# ST-Link_v3_devkit.net
KiCad netlist of a schematic drawn in EasyEDA Pro
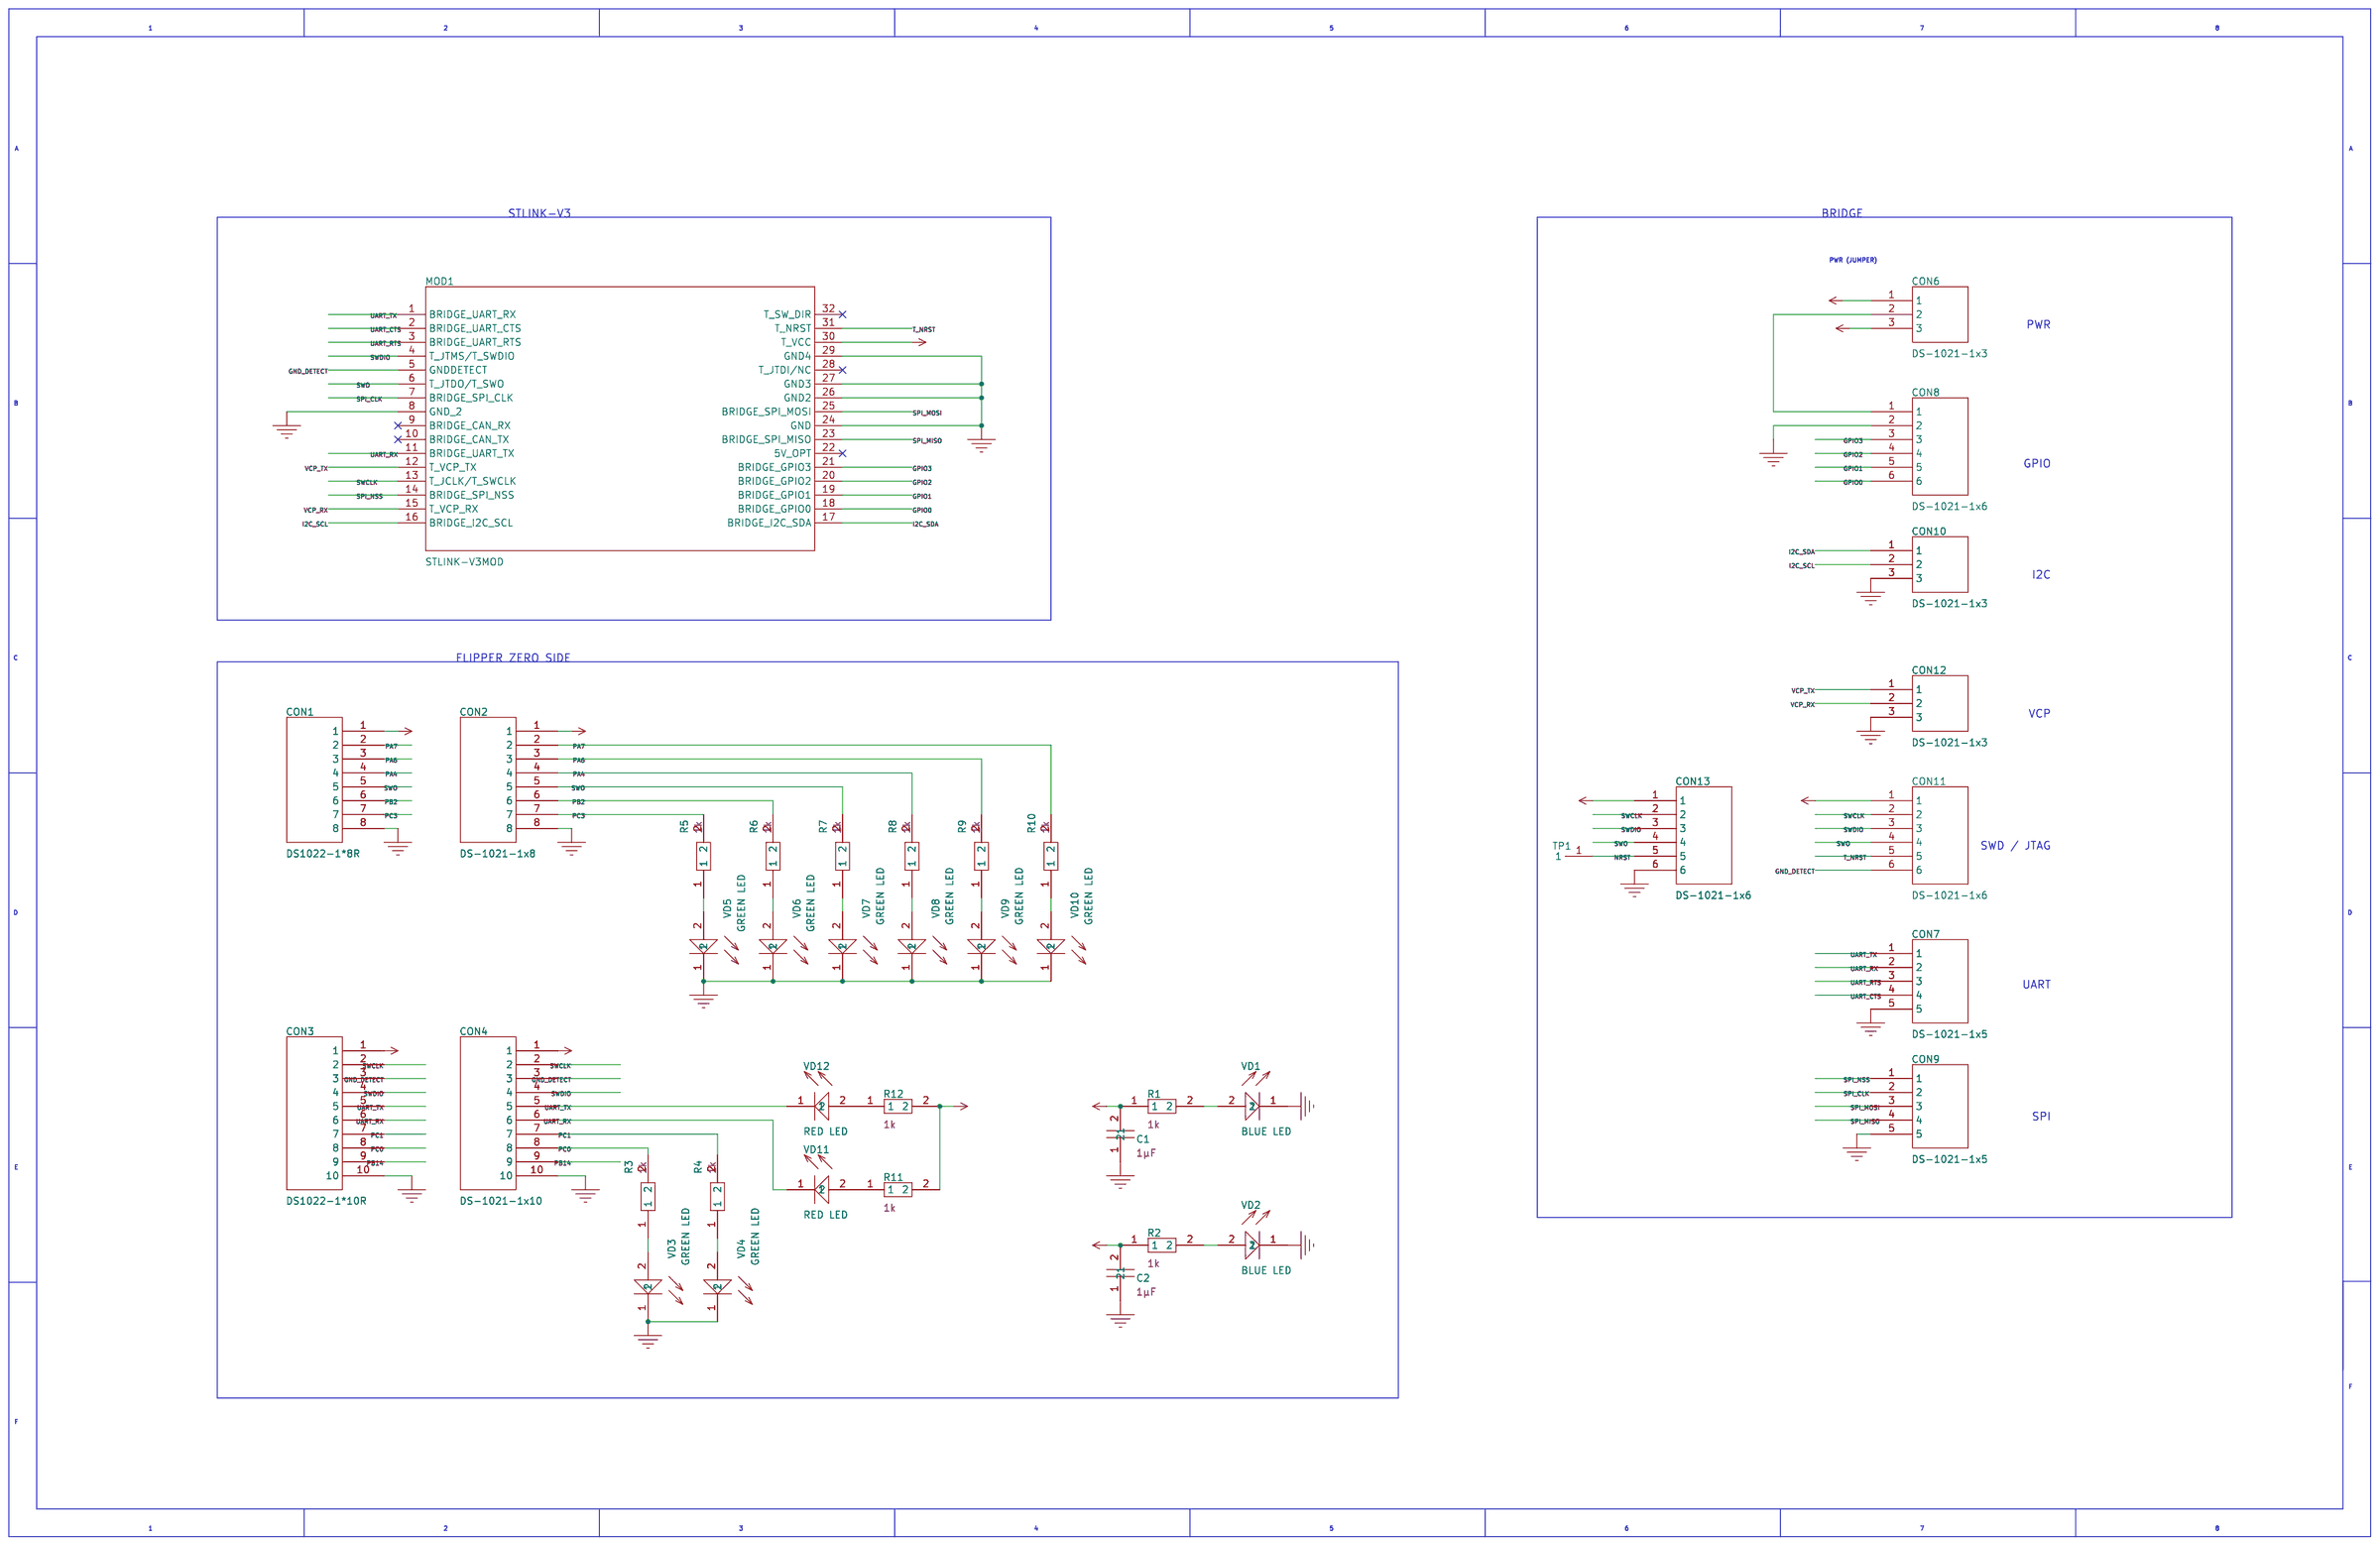
[diagram p0: schematic sheet]

(export (version "E")
  (design (tool "Eeschema 10.0.6"))
  (components
    (comp (ref "C1")
      (value "1µF")
      (footprint "easyedapro:Capacitor_SMD:C_0603_1608Metric")
      (description "Chip Capacitor")
      (fields (field (name "TOLERANCE") "10%") (field (name "VOLTAGE") "16V"))
      (libsource (lib "easyedapro") (part "ST-Link_3.0_devkit-altium-import_root_1_Symbol"))
    )
    (comp (ref "C2")
      (value "1µF")
      (footprint "easyedapro:Capacitor_SMD:C_0603_1608Metric")
      (description "Chip Capacitor")
      (fields (field (name "TOLERANCE") "10%") (field (name "VOLTAGE") "16V"))
      (libsource (lib "easyedapro") (part "ST-Link_3.0_devkit-altium-import_root_1_Symbol"))
    )
    (comp (ref "CON1")
      (value "DS1022-1*8R")
      (footprint "easyedapro:Connector_PinHeader_2.54mm:PinHeader_1x08_P2.54mm_Vertical")
      (description "Connector 2.54mm 1х8 Angular Type")
      (libsource (lib "easyedapro") (part "ST-Link_3.0_devkit-altium-import_root_0_DS-1022-1x8"))
    )
    (comp (ref "CON2")
      (value "DS-1021-1x8")
      (footprint "easyedapro:Connector_PinHeader_2.54mm:PinHeader_1x08_P2.54mm_Vertical")
      (description "Connector 2.54mm 1х8 Straight Type")
      (libsource (lib "easyedapro") (part "ST-Link_3.0_devkit-altium-import_root_0_DS-1022-1x8"))
    )
    (comp (ref "CON3")
      (value "DS1022-1*10R")
      (footprint "easyedapro:Connector_PinHeader_2.54mm:PinHeader_1x10_P2.54mm_Horizontal")
      (description "Connector 2.54mm 1х10 Angular Type")
      (libsource (lib "easyedapro") (part "ST-Link_3.0_devkit-altium-import_root_0_DS-1022-1x10"))
    )
    (comp (ref "CON4")
      (value "DS-1021-1x10")
      (footprint "easyedapro:Connector_PinHeader_2.54mm:PinHeader_1x10_P2.54mm_Vertical")
      (description "Connector 2.54mm 1х10 Straight Type")
      (libsource (lib "easyedapro") (part "ST-Link_3.0_devkit-altium-import_root_0_DS-1021-1x10"))
    )
    (comp (ref "CON6")
      (value "DS-1021-1x3")
      (footprint "easyedapro:Connector_PinHeader_2.54mm:PinHeader_1x03_P2.54mm_Vertical")
      (description "Connector 2.54mm 1х3 Straight Type")
      (libsource (lib "easyedapro") (part "ST-Link_3.0_devkit-altium-import_root_0_mirrored_DS-1021-1x3"))
    )
    (comp (ref "CON7")
      (value "DS-1021-1x5")
      (footprint "easyedapro:Connector_PinHeader_2.54mm:PinHeader_1x05_P2.54mm_Vertical")
      (description "Connector 2.54mm 1х5 Straight Type")
      (libsource (lib "easyedapro") (part "ST-Link_3.0_devkit-altium-import_root_0_mirrored_DS-1021-1x5"))
    )
    (comp (ref "CON8")
      (value "DS-1021-1x6")
      (footprint "easyedapro:Connector_PinHeader_2.54mm:PinHeader_1x06_P2.54mm_Vertical")
      (description "Connector 2.54mm 1х6 Straight Type")
      (libsource (lib "easyedapro") (part "ST-Link_3.0_devkit-altium-import_root_0_mirrored_DS-1021-1x6"))
    )
    (comp (ref "CON9")
      (value "DS-1021-1x5")
      (footprint "easyedapro:Connector_PinHeader_2.54mm:PinHeader_1x05_P2.54mm_Vertical")
      (description "Connector 2.54mm 1х5 Straight Type")
      (libsource (lib "easyedapro") (part "ST-Link_3.0_devkit-altium-import_root_0_mirrored_DS-1021-1x5"))
    )
    (comp (ref "CON10")
      (value "DS-1021-1x3")
      (footprint "easyedapro:Connector_PinHeader_2.54mm:PinHeader_1x03_P2.54mm_Vertical")
      (description "Connector 2.54mm 1х3 Straight Type")
      (libsource (lib "easyedapro") (part "ST-Link_3.0_devkit-altium-import_root_0_mirrored_DS-1021-1x3"))
    )
    (comp (ref "CON11")
      (value "DS-1021-1x6")
      (footprint "easyedapro:Connector_PinHeader_2.54mm:PinHeader_1x06_P2.54mm_Vertical")
      (description "Connector 2.54mm 1х6 Straight Type")
      (libsource (lib "easyedapro") (part "ST-Link_3.0_devkit-altium-import_root_0_mirrored_DS-1021-1x6"))
    )
    (comp (ref "CON12")
      (value "DS-1021-1x3")
      (footprint "easyedapro:Connector_PinHeader_2.54mm:PinHeader_1x03_P2.54mm_Vertical")
      (description "Connector 2.54mm 1х3 Straight Type")
      (libsource (lib "easyedapro") (part "ST-Link_3.0_devkit-altium-import_root_0_mirrored_DS-1021-1x3"))
    )
    (comp (ref "CON13")
      (value "DS-1021-1x6")
      (footprint "easyedapro:Connector_PinHeader_2.54mm:PinHeader_1x06_P2.54mm_Vertical")
      (description "Connector 2.54mm 1х6 Straight Type")
      (libsource (lib "easyedapro") (part "ST-Link_3.0_devkit-altium-import_root_0_mirrored_DS-1021-1x6"))
    )
    (comp (ref "MOD1")
      (value "STLINK-V3MOD")
      (footprint "easyedapro:Library:MODULE_STLINK-V3MODS")
      (description "STLINK-V3 Compact In-Circuit Debugger and Programmer for STM32 Microcontroller")
      (libsource (lib "easyedapro") (part "ST-Link_3.0_devkit-altium-import_root_0_STLINK-V3MOD"))
    )
    (comp (ref "R1")
      (value "1k")
      (footprint "easyedapro:Resistor_SMD:R_0603_1608Metric")
      (description "Chip Resistor, 1 KOhm, +/-5%, 0.1 W, -55 to 155 degC, 0603 (1608 Metric)")
      (fields (field (name "POWER") "100mW") (field (name "TOLERANCE") "5%"))
      (libsource (lib "easyedapro") (part "ST-Link_3.0_devkit-altium-import_root_2_Symbol"))
    )
    (comp (ref "R2")
      (value "1k")
      (footprint "easyedapro:Resistor_SMD:R_0603_1608Metric")
      (description "Chip Resistor, 1 KOhm, +/-5%, 0.1 W, -55 to 155 degC, 0603 (1608 Metric)")
      (fields (field (name "POWER") "100mW") (field (name "TOLERANCE") "5%"))
      (libsource (lib "easyedapro") (part "ST-Link_3.0_devkit-altium-import_root_2_Symbol"))
    )
    (comp (ref "R3")
      (value "1k")
      (footprint "easyedapro:Resistor_SMD:R_0603_1608Metric")
      (description "Chip Resistor, 1 KOhm, +/-5%, 0.1 W, -55 to 155 degC, 0603 (1608 Metric)")
      (fields (field (name "POWER") "100mW") (field (name "TOLERANCE") "5%"))
      (libsource (lib "easyedapro") (part "ST-Link_3.0_devkit-altium-import_root_2_Symbol"))
    )
    (comp (ref "R4")
      (value "1k")
      (footprint "easyedapro:Resistor_SMD:R_0603_1608Metric")
      (description "Chip Resistor, 1 KOhm, +/-5%, 0.1 W, -55 to 155 degC, 0603 (1608 Metric)")
      (fields (field (name "POWER") "100mW") (field (name "TOLERANCE") "5%"))
      (libsource (lib "easyedapro") (part "ST-Link_3.0_devkit-altium-import_root_2_Symbol"))
    )
    (comp (ref "R5")
      (value "1k")
      (footprint "easyedapro:Resistor_SMD:R_0603_1608Metric")
      (description "Chip Resistor, 1 KOhm, +/-5%, 0.1 W, -55 to 155 degC, 0603 (1608 Metric)")
      (fields (field (name "POWER") "100mW") (field (name "TOLERANCE") "5%"))
      (libsource (lib "easyedapro") (part "ST-Link_3.0_devkit-altium-import_root_2_Symbol"))
    )
    (comp (ref "R6")
      (value "1k")
      (footprint "easyedapro:Resistor_SMD:R_0603_1608Metric")
      (description "Chip Resistor, 1 KOhm, +/-5%, 0.1 W, -55 to 155 degC, 0603 (1608 Metric)")
      (fields (field (name "POWER") "100mW") (field (name "TOLERANCE") "5%"))
      (libsource (lib "easyedapro") (part "ST-Link_3.0_devkit-altium-import_root_2_Symbol"))
    )
    (comp (ref "R7")
      (value "1k")
      (footprint "easyedapro:Resistor_SMD:R_0603_1608Metric")
      (description "Chip Resistor, 1 KOhm, +/-5%, 0.1 W, -55 to 155 degC, 0603 (1608 Metric)")
      (fields (field (name "POWER") "100mW") (field (name "TOLERANCE") "5%"))
      (libsource (lib "easyedapro") (part "ST-Link_3.0_devkit-altium-import_root_2_Symbol"))
    )
    (comp (ref "R8")
      (value "1k")
      (footprint "easyedapro:Resistor_SMD:R_0603_1608Metric")
      (description "Chip Resistor, 1 KOhm, +/-5%, 0.1 W, -55 to 155 degC, 0603 (1608 Metric)")
      (fields (field (name "POWER") "100mW") (field (name "TOLERANCE") "5%"))
      (libsource (lib "easyedapro") (part "ST-Link_3.0_devkit-altium-import_root_2_Symbol"))
    )
    (comp (ref "R9")
      (value "1k")
      (footprint "easyedapro:Resistor_SMD:R_0603_1608Metric")
      (description "Chip Resistor, 1 KOhm, +/-5%, 0.1 W, -55 to 155 degC, 0603 (1608 Metric)")
      (fields (field (name "POWER") "100mW") (field (name "TOLERANCE") "5%"))
      (libsource (lib "easyedapro") (part "ST-Link_3.0_devkit-altium-import_root_2_Symbol"))
    )
    (comp (ref "R10")
      (value "1k")
      (footprint "easyedapro:Resistor_SMD:R_0603_1608Metric")
      (description "Chip Resistor, 1 KOhm, +/-5%, 0.1 W, -55 to 155 degC, 0603 (1608 Metric)")
      (fields (field (name "POWER") "100mW") (field (name "TOLERANCE") "5%"))
      (libsource (lib "easyedapro") (part "ST-Link_3.0_devkit-altium-import_root_2_Symbol"))
    )
    (comp (ref "R11")
      (value "1k")
      (footprint "easyedapro:Resistor_SMD:R_0603_1608Metric")
      (description "Chip Resistor, 1 KOhm, +/-5%, 0.1 W, -55 to 155 degC, 0603 (1608 Metric)")
      (fields (field (name "POWER") "100mW") (field (name "TOLERANCE") "5%"))
      (libsource (lib "easyedapro") (part "ST-Link_3.0_devkit-altium-import_root_2_Symbol"))
    )
    (comp (ref "R12")
      (value "1k")
      (footprint "easyedapro:Resistor_SMD:R_0603_1608Metric")
      (description "Chip Resistor, 1 KOhm, +/-5%, 0.1 W, -55 to 155 degC, 0603 (1608 Metric)")
      (fields (field (name "POWER") "100mW") (field (name "TOLERANCE") "5%"))
      (libsource (lib "easyedapro") (part "ST-Link_3.0_devkit-altium-import_root_2_Symbol"))
    )
    (comp (ref "TP1")
      (value "Control_point")
      (footprint "easyedapro:TestPoint:TestPoint_Pad_D1.0mm")
      (description "Testpoint")
      (libsource (lib "easyedapro") (part "ST-Link_3.0_devkit-altium-import_root_2_control point"))
    )
    (comp (ref "VD1")
      (value "BLUE LED")
      (description "LED")
      (libsource (lib "easyedapro") (part "ST-Link_3.0_devkit-altium-import_root_0_VSMY14940"))
    )
    (comp (ref "VD2")
      (value "BLUE LED")
      (description "LED")
      (libsource (lib "easyedapro") (part "ST-Link_3.0_devkit-altium-import_root_0_VSMY14940"))
    )
    (comp (ref "VD3")
      (value "GREEN LED")
      (footprint "easyedapro:LED_SMD:LED_0603_1608Metric")
      (description "LED")
      (libsource (lib "easyedapro") (part "ST-Link_3.0_devkit-altium-import_root_3_VSMY14940"))
    )
    (comp (ref "VD4")
      (value "GREEN LED")
      (footprint "easyedapro:LED_SMD:LED_0603_1608Metric")
      (description "LED")
      (libsource (lib "easyedapro") (part "ST-Link_3.0_devkit-altium-import_root_3_VSMY14940"))
    )
    (comp (ref "VD5")
      (value "GREEN LED")
      (footprint "easyedapro:LED_SMD:LED_0603_1608Metric")
      (description "LED")
      (libsource (lib "easyedapro") (part "ST-Link_3.0_devkit-altium-import_root_3_VSMY14940"))
    )
    (comp (ref "VD6")
      (value "GREEN LED")
      (footprint "easyedapro:LED_SMD:LED_0603_1608Metric")
      (description "LED")
      (libsource (lib "easyedapro") (part "ST-Link_3.0_devkit-altium-import_root_3_VSMY14940"))
    )
    (comp (ref "VD7")
      (value "GREEN LED")
      (footprint "easyedapro:LED_SMD:LED_0603_1608Metric")
      (description "LED")
      (libsource (lib "easyedapro") (part "ST-Link_3.0_devkit-altium-import_root_3_VSMY14940"))
    )
    (comp (ref "VD8")
      (value "GREEN LED")
      (footprint "easyedapro:LED_SMD:LED_0603_1608Metric")
      (description "LED")
      (libsource (lib "easyedapro") (part "ST-Link_3.0_devkit-altium-import_root_3_VSMY14940"))
    )
    (comp (ref "VD9")
      (value "GREEN LED")
      (footprint "easyedapro:LED_SMD:LED_0603_1608Metric")
      (description "LED")
      (libsource (lib "easyedapro") (part "ST-Link_3.0_devkit-altium-import_root_3_VSMY14940"))
    )
    (comp (ref "VD10")
      (value "GREEN LED")
      (footprint "easyedapro:LED_SMD:LED_0603_1608Metric")
      (description "LED")
      (libsource (lib "easyedapro") (part "ST-Link_3.0_devkit-altium-import_root_3_VSMY14940"))
    )
    (comp (ref "VD11")
      (value "RED LED")
      (description "LED")
      (libsource (lib "easyedapro") (part "ST-Link_3.0_devkit-altium-import_root_0_mirrored_VSMY14940"))
    )
    (comp (ref "VD12")
      (value "RED LED")
      (description "LED")
      (libsource (lib "easyedapro") (part "ST-Link_3.0_devkit-altium-import_root_0_mirrored_VSMY14940"))
    )
  )
  (nets
    (net (code "1") (name "/GND_DETECT") (class "Default")
      (node (ref "CON11") (pin "6") (pinfunction "6_6") (pintype "unspecified"))
      (node (ref "CON3") (pin "3") (pinfunction "3_3") (pintype "unspecified"))
      (node (ref "CON4") (pin "3") (pinfunction "3_3") (pintype "unspecified"))
      (node (ref "MOD1") (pin "5") (pinfunction "GNDDETECT_5") (pintype "unspecified"))
    )
    (net (code "2") (name "/GPIO0") (class "Default")
      (node (ref "CON8") (pin "6") (pinfunction "6_6") (pintype "unspecified"))
      (node (ref "MOD1") (pin "18") (pinfunction "BRIDGE_GPIO0_18") (pintype "bidirectional"))
    )
    (net (code "3") (name "/GPIO1") (class "Default")
      (node (ref "CON8") (pin "5") (pinfunction "5_5") (pintype "unspecified"))
      (node (ref "MOD1") (pin "19") (pinfunction "BRIDGE_GPIO1_19") (pintype "bidirectional"))
    )
    (net (code "4") (name "/GPIO2") (class "Default")
      (node (ref "CON8") (pin "4") (pinfunction "4_4") (pintype "unspecified"))
      (node (ref "MOD1") (pin "20") (pinfunction "BRIDGE_GPIO2_20") (pintype "bidirectional"))
    )
    (net (code "5") (name "/GPIO3") (class "Default")
      (node (ref "CON8") (pin "3") (pinfunction "3_3") (pintype "unspecified"))
      (node (ref "MOD1") (pin "21") (pinfunction "BRIDGE_GPIO3_21") (pintype "bidirectional"))
    )
    (net (code "6") (name "/I2C_SCL") (class "Default")
      (node (ref "CON10") (pin "2") (pinfunction "2_2") (pintype "unspecified"))
      (node (ref "MOD1") (pin "16") (pinfunction "BRIDGE_I2C_SCL_16") (pintype "bidirectional"))
    )
    (net (code "7") (name "/I2C_SDA") (class "Default")
      (node (ref "CON10") (pin "1") (pinfunction "1_1") (pintype "unspecified"))
      (node (ref "MOD1") (pin "17") (pinfunction "BRIDGE_I2C_SDA_17") (pintype "bidirectional"))
    )
    (net (code "8") (name "/NRST") (class "Default")
      (node (ref "CON13") (pin "5") (pinfunction "5_5") (pintype "unspecified"))
      (node (ref "TP1") (pin "1") (pinfunction "1_1") (pintype "unspecified"))
    )
    (net (code "9") (name "/PA4") (class "Default")
      (node (ref "CON1") (pin "4") (pinfunction "4_4") (pintype "unspecified"))
      (node (ref "CON2") (pin "4") (pinfunction "4_4") (pintype "unspecified"))
      (node (ref "R8") (pin "2") (pinfunction "2_2") (pintype "unspecified"))
    )
    (net (code "10") (name "/PA6") (class "Default")
      (node (ref "CON1") (pin "3") (pinfunction "3_3") (pintype "unspecified"))
      (node (ref "CON2") (pin "3") (pinfunction "3_3") (pintype "unspecified"))
      (node (ref "R9") (pin "2") (pinfunction "2_2") (pintype "unspecified"))
    )
    (net (code "11") (name "/PA7") (class "Default")
      (node (ref "CON1") (pin "2") (pinfunction "2_2") (pintype "unspecified"))
      (node (ref "CON2") (pin "2") (pinfunction "2_2") (pintype "unspecified"))
      (node (ref "R10") (pin "2") (pinfunction "2_2") (pintype "unspecified"))
    )
    (net (code "12") (name "/PB2") (class "Default")
      (node (ref "CON1") (pin "6") (pinfunction "6_6") (pintype "unspecified"))
      (node (ref "CON2") (pin "6") (pinfunction "6_6") (pintype "unspecified"))
      (node (ref "R6") (pin "2") (pinfunction "2_2") (pintype "unspecified"))
    )
    (net (code "13") (name "/PB14") (class "Default")
      (node (ref "CON3") (pin "9") (pinfunction "9_9") (pintype "unspecified"))
      (node (ref "CON4") (pin "9") (pinfunction "9_9") (pintype "unspecified"))
    )
    (net (code "14") (name "/PC0") (class "Default")
      (node (ref "CON3") (pin "8") (pinfunction "8_8") (pintype "unspecified"))
      (node (ref "CON4") (pin "8") (pinfunction "8_8") (pintype "unspecified"))
      (node (ref "R3") (pin "2") (pinfunction "2_2") (pintype "unspecified"))
    )
    (net (code "15") (name "/PC1") (class "Default")
      (node (ref "CON3") (pin "7") (pinfunction "7_7") (pintype "unspecified"))
      (node (ref "CON4") (pin "7") (pinfunction "7_7") (pintype "unspecified"))
      (node (ref "R4") (pin "2") (pinfunction "2_2") (pintype "unspecified"))
    )
    (net (code "16") (name "/PC3") (class "Default")
      (node (ref "CON1") (pin "7") (pinfunction "7_7") (pintype "unspecified"))
      (node (ref "CON2") (pin "7") (pinfunction "7_7") (pintype "unspecified"))
      (node (ref "R5") (pin "2") (pinfunction "2_2") (pintype "unspecified"))
    )
    (net (code "17") (name "/SPI_CLK") (class "Default")
      (node (ref "CON9") (pin "2") (pinfunction "2_2") (pintype "unspecified"))
      (node (ref "MOD1") (pin "7") (pinfunction "BRIDGE_SPI_CLK_7") (pintype "unspecified"))
    )
    (net (code "18") (name "/SPI_MISO") (class "Default")
      (node (ref "CON9") (pin "4") (pinfunction "4_4") (pintype "unspecified"))
      (node (ref "MOD1") (pin "23") (pinfunction "BRIDGE_SPI_MISO_23") (pintype "unspecified"))
    )
    (net (code "19") (name "/SPI_MOSI") (class "Default")
      (node (ref "CON9") (pin "3") (pinfunction "3_3") (pintype "unspecified"))
      (node (ref "MOD1") (pin "25") (pinfunction "BRIDGE_SPI_MOSI_25") (pintype "unspecified"))
    )
    (net (code "20") (name "/SPI_NSS") (class "Default")
      (node (ref "CON9") (pin "1") (pinfunction "1_1") (pintype "unspecified"))
      (node (ref "MOD1") (pin "14") (pinfunction "BRIDGE_SPI_NSS_14") (pintype "unspecified"))
    )
    (net (code "21") (name "/SWCLK") (class "Default")
      (node (ref "CON11") (pin "2") (pinfunction "2_2") (pintype "unspecified"))
      (node (ref "CON13") (pin "2") (pinfunction "2_2") (pintype "unspecified"))
      (node (ref "CON3") (pin "2") (pinfunction "2_2") (pintype "unspecified"))
      (node (ref "CON4") (pin "2") (pinfunction "2_2") (pintype "unspecified"))
      (node (ref "MOD1") (pin "13") (pinfunction "T_JCLK/T_SWCLK_13") (pintype "unspecified"))
    )
    (net (code "22") (name "/SWDIO") (class "Default")
      (node (ref "CON11") (pin "3") (pinfunction "3_3") (pintype "unspecified"))
      (node (ref "CON13") (pin "3") (pinfunction "3_3") (pintype "unspecified"))
      (node (ref "CON3") (pin "4") (pinfunction "4_4") (pintype "unspecified"))
      (node (ref "CON4") (pin "4") (pinfunction "4_4") (pintype "unspecified"))
      (node (ref "MOD1") (pin "4") (pinfunction "T_JTMS/T_SWDIO_4") (pintype "unspecified"))
    )
    (net (code "23") (name "/SWO") (class "Default")
      (node (ref "CON1") (pin "5") (pinfunction "5_5") (pintype "unspecified"))
      (node (ref "CON11") (pin "4") (pinfunction "4_4") (pintype "unspecified"))
      (node (ref "CON13") (pin "4") (pinfunction "4_4") (pintype "unspecified"))
      (node (ref "CON2") (pin "5") (pinfunction "5_5") (pintype "unspecified"))
      (node (ref "MOD1") (pin "6") (pinfunction "T_JTDO/T_SWO_6") (pintype "unspecified"))
      (node (ref "R7") (pin "2") (pinfunction "2_2") (pintype "unspecified"))
    )
    (net (code "24") (name "/T_NRST") (class "Default")
      (node (ref "CON11") (pin "5") (pinfunction "5_5") (pintype "unspecified"))
      (node (ref "MOD1") (pin "31") (pinfunction "T_NRST_31") (pintype "unspecified"))
    )
    (net (code "25") (name "/UART_CTS") (class "Default")
      (node (ref "CON7") (pin "4") (pinfunction "4_4") (pintype "unspecified"))
      (node (ref "MOD1") (pin "2") (pinfunction "BRIDGE_UART_CTS_2") (pintype "unspecified"))
    )
    (net (code "26") (name "/UART_RTS") (class "Default")
      (node (ref "CON7") (pin "3") (pinfunction "3_3") (pintype "unspecified"))
      (node (ref "MOD1") (pin "3") (pinfunction "BRIDGE_UART_RTS_3") (pintype "unspecified"))
    )
    (net (code "27") (name "/UART_RX") (class "Default")
      (node (ref "CON3") (pin "6") (pinfunction "6_6") (pintype "unspecified"))
      (node (ref "CON4") (pin "6") (pinfunction "6_6") (pintype "unspecified"))
      (node (ref "CON7") (pin "2") (pinfunction "2_2") (pintype "unspecified"))
      (node (ref "MOD1") (pin "11") (pinfunction "BRIDGE_UART_TX_11") (pintype "unspecified"))
      (node (ref "VD11") (pin "1") (pinfunction "1_1") (pintype "unspecified"))
    )
    (net (code "28") (name "/UART_TX") (class "Default")
      (node (ref "CON3") (pin "5") (pinfunction "5_5") (pintype "unspecified"))
      (node (ref "CON4") (pin "5") (pinfunction "5_5") (pintype "unspecified"))
      (node (ref "CON7") (pin "1") (pinfunction "1_1") (pintype "unspecified"))
      (node (ref "MOD1") (pin "1") (pinfunction "BRIDGE_UART_RX_1") (pintype "unspecified"))
      (node (ref "VD12") (pin "1") (pinfunction "1_1") (pintype "unspecified"))
    )
    (net (code "29") (name "/VCP_RX") (class "Default")
      (node (ref "CON12") (pin "2") (pinfunction "2_2") (pintype "unspecified"))
      (node (ref "MOD1") (pin "15") (pinfunction "T_VCP_RX_15") (pintype "unspecified"))
    )
    (net (code "30") (name "/VCP_TX") (class "Default")
      (node (ref "CON12") (pin "1") (pinfunction "1_1") (pintype "unspecified"))
      (node (ref "MOD1") (pin "12") (pinfunction "T_VCP_TX_12") (pintype "unspecified"))
    )
    (net (code "31") (name "Net-(CON6-Pad2)") (class "Default")
      (node (ref "CON6") (pin "2") (pinfunction "2_2") (pintype "unspecified"))
      (node (ref "CON8") (pin "1") (pinfunction "1_1") (pintype "unspecified"))
    )
    (net (code "32") (name "Net-(R1-Pad2)") (class "Default")
      (node (ref "R1") (pin "2") (pinfunction "2_2") (pintype "unspecified"))
      (node (ref "VD1") (pin "2") (pinfunction "2_2") (pintype "unspecified"))
    )
    (net (code "33") (name "Net-(R2-Pad2)") (class "Default")
      (node (ref "R2") (pin "2") (pinfunction "2_2") (pintype "unspecified"))
      (node (ref "VD2") (pin "2") (pinfunction "2_2") (pintype "unspecified"))
    )
    (net (code "34") (name "Net-(R3-Pad1)") (class "Default")
      (node (ref "R3") (pin "1") (pinfunction "1_1") (pintype "unspecified"))
      (node (ref "VD3") (pin "2") (pinfunction "2_2") (pintype "unspecified"))
    )
    (net (code "35") (name "Net-(R4-Pad1)") (class "Default")
      (node (ref "R4") (pin "1") (pinfunction "1_1") (pintype "unspecified"))
      (node (ref "VD4") (pin "2") (pinfunction "2_2") (pintype "unspecified"))
    )
    (net (code "36") (name "Net-(R5-Pad1)") (class "Default")
      (node (ref "R5") (pin "1") (pinfunction "1_1") (pintype "unspecified"))
      (node (ref "VD5") (pin "2") (pinfunction "2_2") (pintype "unspecified"))
    )
    (net (code "37") (name "Net-(R6-Pad1)") (class "Default")
      (node (ref "R6") (pin "1") (pinfunction "1_1") (pintype "unspecified"))
      (node (ref "VD6") (pin "2") (pinfunction "2_2") (pintype "unspecified"))
    )
    (net (code "38") (name "Net-(R7-Pad1)") (class "Default")
      (node (ref "R7") (pin "1") (pinfunction "1_1") (pintype "unspecified"))
      (node (ref "VD7") (pin "2") (pinfunction "2_2") (pintype "unspecified"))
    )
    (net (code "39") (name "Net-(R8-Pad1)") (class "Default")
      (node (ref "R8") (pin "1") (pinfunction "1_1") (pintype "unspecified"))
      (node (ref "VD8") (pin "2") (pinfunction "2_2") (pintype "unspecified"))
    )
    (net (code "40") (name "Net-(R9-Pad1)") (class "Default")
      (node (ref "R9") (pin "1") (pinfunction "1_1") (pintype "unspecified"))
      (node (ref "VD9") (pin "2") (pinfunction "2_2") (pintype "unspecified"))
    )
    (net (code "41") (name "Net-(R10-Pad1)") (class "Default")
      (node (ref "R10") (pin "1") (pinfunction "1_1") (pintype "unspecified"))
      (node (ref "VD10") (pin "2") (pinfunction "2_2") (pintype "unspecified"))
    )
    (net (code "42") (name "Net-(R11-Pad1)") (class "Default")
      (node (ref "R11") (pin "1") (pinfunction "1_1") (pintype "unspecified"))
      (node (ref "VD11") (pin "2") (pinfunction "2_2") (pintype "unspecified"))
    )
    (net (code "43") (name "Net-(R12-Pad1)") (class "Default")
      (node (ref "R12") (pin "1") (pinfunction "1_1") (pintype "unspecified"))
      (node (ref "VD12") (pin "2") (pinfunction "2_2") (pintype "unspecified"))
    )
    (net (code "44") (name "ST-LINK_3.0_DEVKIT-ALTIUM-IMPORT_3V3_GOST_ARROW") (class "Default")
      (node (ref "C2") (pin "2") (pinfunction "2_2") (pintype "unspecified"))
      (node (ref "CON11") (pin "1") (pinfunction "1_1") (pintype "unspecified"))
      (node (ref "CON13") (pin "1") (pinfunction "1_1") (pintype "unspecified"))
      (node (ref "CON3") (pin "1") (pinfunction "1_1") (pintype "unspecified"))
      (node (ref "CON4") (pin "1") (pinfunction "1_1") (pintype "unspecified"))
      (node (ref "CON6") (pin "3") (pinfunction "3_3") (pintype "unspecified"))
      (node (ref "MOD1") (pin "30") (pinfunction "T_VCC_30") (pintype "unspecified"))
      (node (ref "R11") (pin "2") (pinfunction "2_2") (pintype "unspecified"))
      (node (ref "R12") (pin "2") (pinfunction "2_2") (pintype "unspecified"))
      (node (ref "R2") (pin "1") (pinfunction "1_1") (pintype "unspecified"))
    )
    (net (code "45") (name "ST-LINK_3.0_DEVKIT-ALTIUM-IMPORT_5V_GOST_ARROW") (class "Default")
      (node (ref "C1") (pin "2") (pinfunction "2_2") (pintype "unspecified"))
      (node (ref "CON1") (pin "1") (pinfunction "1_1") (pintype "unspecified"))
      (node (ref "CON2") (pin "1") (pinfunction "1_1") (pintype "unspecified"))
      (node (ref "CON6") (pin "1") (pinfunction "1_1") (pintype "unspecified"))
      (node (ref "R1") (pin "1") (pinfunction "1_1") (pintype "unspecified"))
    )
    (net (code "46") (name "ST-LINK_3.0_DEVKIT-ALTIUM-IMPORT_GND_POWER_GROUND") (class "Default")
      (node (ref "C1") (pin "1") (pinfunction "1_1") (pintype "unspecified"))
      (node (ref "C2") (pin "1") (pinfunction "1_1") (pintype "unspecified"))
      (node (ref "CON1") (pin "8") (pinfunction "8_8") (pintype "unspecified"))
      (node (ref "CON10") (pin "3") (pinfunction "3_3") (pintype "unspecified"))
      (node (ref "CON12") (pin "3") (pinfunction "3_3") (pintype "unspecified"))
      (node (ref "CON13") (pin "6") (pinfunction "6_6") (pintype "unspecified"))
      (node (ref "CON2") (pin "8") (pinfunction "8_8") (pintype "unspecified"))
      (node (ref "CON3") (pin "10") (pinfunction "10_10") (pintype "unspecified"))
      (node (ref "CON4") (pin "10") (pinfunction "10_10") (pintype "unspecified"))
      (node (ref "CON7") (pin "5") (pinfunction "5_5") (pintype "unspecified"))
      (node (ref "CON8") (pin "2") (pinfunction "2_2") (pintype "unspecified"))
      (node (ref "CON9") (pin "5") (pinfunction "5_5") (pintype "unspecified"))
      (node (ref "MOD1") (pin "24") (pinfunction "GND_24") (pintype "unspecified"))
      (node (ref "MOD1") (pin "26") (pinfunction "GND2_26") (pintype "unspecified"))
      (node (ref "MOD1") (pin "27") (pinfunction "GND3_27") (pintype "unspecified"))
      (node (ref "MOD1") (pin "29") (pinfunction "GND4_29") (pintype "unspecified"))
      (node (ref "MOD1") (pin "8") (pinfunction "GND_2_8") (pintype "unspecified"))
      (node (ref "VD1") (pin "1") (pinfunction "1_1") (pintype "unspecified"))
      (node (ref "VD10") (pin "1") (pinfunction "1_1") (pintype "unspecified"))
      (node (ref "VD2") (pin "1") (pinfunction "1_1") (pintype "unspecified"))
      (node (ref "VD3") (pin "1") (pinfunction "1_1") (pintype "unspecified"))
      (node (ref "VD4") (pin "1") (pinfunction "1_1") (pintype "unspecified"))
      (node (ref "VD5") (pin "1") (pinfunction "1_1") (pintype "unspecified"))
      (node (ref "VD6") (pin "1") (pinfunction "1_1") (pintype "unspecified"))
      (node (ref "VD7") (pin "1") (pinfunction "1_1") (pintype "unspecified"))
      (node (ref "VD8") (pin "1") (pinfunction "1_1") (pintype "unspecified"))
      (node (ref "VD9") (pin "1") (pinfunction "1_1") (pintype "unspecified"))
    )
    (net (code "47") (name "unconnected-(MOD1-5V_OPT-Pad22)") (class "Default")
      (node (ref "MOD1") (pin "22") (pinfunction "5V_OPT_22") (pintype "unspecified+no_connect"))
    )
    (net (code "48") (name "unconnected-(MOD1-BRIDGE_CAN_RX-Pad9)") (class "Default")
      (node (ref "MOD1") (pin "9") (pinfunction "BRIDGE_CAN_RX_9") (pintype "unspecified+no_connect"))
    )
    (net (code "49") (name "unconnected-(MOD1-BRIDGE_CAN_TX-Pad10)") (class "Default")
      (node (ref "MOD1") (pin "10") (pinfunction "BRIDGE_CAN_TX_10") (pintype "unspecified+no_connect"))
    )
    (net (code "50") (name "unconnected-(MOD1-T_JTDI{slash}NC-Pad28)") (class "Default")
      (node (ref "MOD1") (pin "28") (pinfunction "T_JTDI/NC_28") (pintype "unspecified+no_connect"))
    )
    (net (code "51") (name "unconnected-(MOD1-T_SW_DIR-Pad32)") (class "Default")
      (node (ref "MOD1") (pin "32") (pinfunction "T_SW_DIR_32") (pintype "unspecified+no_connect"))
    )
  )
)
